# Main.net
KiCad netlist of a schematic drawn in EAGLE
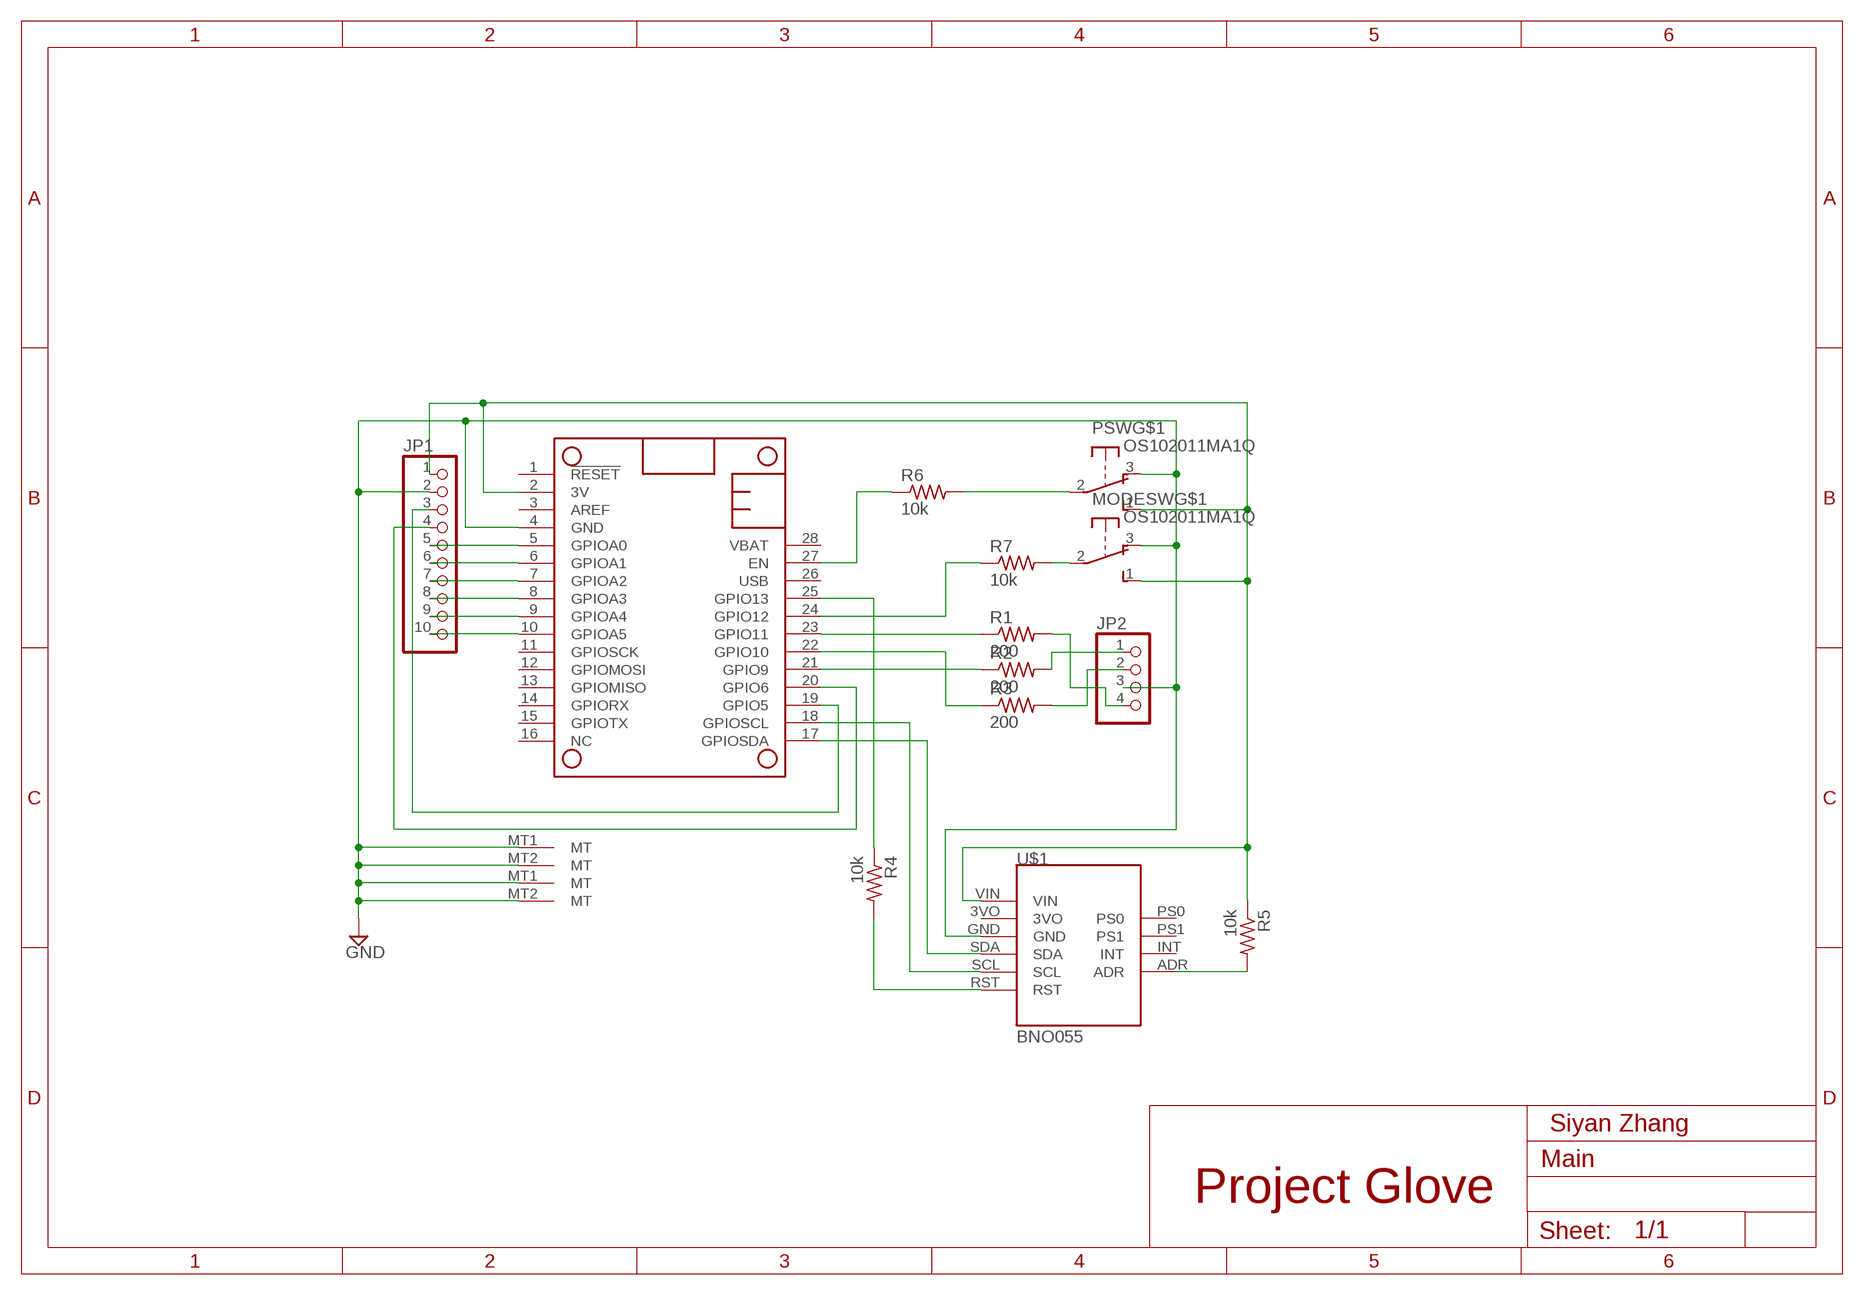
[diagram p0: schematic, sheet 1]

(export (version "E")
  (design (tool "Eeschema 10.0.6"))
  (components
    (comp (ref "JP1")
      (value "PINHD-1X10")
      (footprint "eagle-import:1X10")
      (libsource (lib "eagle-import") (part "PINHD-1X10"))
    )
    (comp (ref "JP2")
      (value "PINHD-1X4")
      (footprint "eagle-import:1X04")
      (libsource (lib "eagle-import") (part "PINHD-1X4"))
    )
    (comp (ref "MODESW")
      (value "OS102011MA1Q")
      (footprint "eagle-import:OS102011MA1Q")
      (libsource (lib "eagle-import") (part "OS102011MA1Q"))
    )
    (comp (ref "MS1")
      (value "FEATHERWING")
      (footprint "eagle-import:FEATHERWING")
      (libsource (lib "eagle-import") (part "FEATHERWING"))
    )
    (comp (ref "PSW")
      (value "OS102011MA1Q")
      (footprint "eagle-import:OS102011MA1Q")
      (libsource (lib "eagle-import") (part "OS102011MA1Q"))
    )
    (comp (ref "R1")
      (value "200")
      (footprint "eagle-import:0207_7")
      (libsource (lib "eagle-import") (part "R-US_0207/7"))
    )
    (comp (ref "R2")
      (value "200")
      (footprint "eagle-import:0207_7")
      (libsource (lib "eagle-import") (part "R-US_0207/7"))
    )
    (comp (ref "R3")
      (value "200")
      (footprint "eagle-import:0207_7")
      (libsource (lib "eagle-import") (part "R-US_0207/7"))
    )
    (comp (ref "R4")
      (value "10k")
      (footprint "eagle-import:0207_7")
      (libsource (lib "eagle-import") (part "R-US_0207/7"))
    )
    (comp (ref "R5")
      (value "10k")
      (footprint "eagle-import:0207_15")
      (libsource (lib "eagle-import") (part "R-US_0207/15"))
    )
    (comp (ref "R6")
      (value "10k")
      (footprint "eagle-import:0207_7")
      (libsource (lib "eagle-import") (part "R-US_0207/7"))
    )
    (comp (ref "R7")
      (value "10k")
      (footprint "eagle-import:0207_7")
      (libsource (lib "eagle-import") (part "R-US_0207/7"))
    )
    (comp (ref "U$1")
      (value "BNO055")
      (footprint "eagle-import:BNO055")
      (libsource (lib "eagle-import") (part "BNO055"))
    )
  )
  (nets
    (net (code "1") (name "/USB") (class "Default")
      (node (ref "MS1") (pin "26") (pinfunction "USB_26") (pintype "power_in"))
    )
    (net (code "2") (name "/VBAT") (class "Default")
      (node (ref "MS1") (pin "28") (pinfunction "VBAT_28") (pintype "power_in"))
    )
    (net (code "3") (name "GND") (class "Default")
      (node (ref "JP1") (pin "2") (pinfunction "2_2") (pintype "passive"))
      (node (ref "JP2") (pin "3") (pinfunction "3_3") (pintype "passive"))
      (node (ref "MODESW") (pin "3") (pinfunction "O_3") (pintype "passive"))
      (node (ref "MODESW") (pin "MT1") (pinfunction "MT_MT1") (pintype "passive"))
      (node (ref "MODESW") (pin "MT2") (pinfunction "MT_MT2") (pintype "passive"))
      (node (ref "MS1") (pin "4") (pinfunction "GND_4") (pintype "power_in"))
      (node (ref "PSW") (pin "3") (pinfunction "O_3") (pintype "passive"))
      (node (ref "PSW") (pin "MT1") (pinfunction "MT_MT1") (pintype "passive"))
      (node (ref "PSW") (pin "MT2") (pinfunction "MT_MT2") (pintype "passive"))
      (node (ref "U$1") (pin "GND") (pinfunction "GND_GND") (pintype "input"))
    )
    (net (code "4") (name "Net-(JP2-Pad1)") (class "Default")
      (node (ref "JP2") (pin "1") (pinfunction "1_1") (pintype "passive"))
      (node (ref "R2") (pin "2") (pinfunction "2_2") (pintype "passive"))
    )
    (net (code "5") (name "Net-(JP2-Pad2)") (class "Default")
      (node (ref "JP2") (pin "2") (pinfunction "2_2") (pintype "passive"))
      (node (ref "R3") (pin "2") (pinfunction "2_2") (pintype "passive"))
    )
    (net (code "6") (name "Net-(JP2-Pad4)") (class "Default")
      (node (ref "JP2") (pin "4") (pinfunction "4_4") (pintype "passive"))
      (node (ref "R1") (pin "2") (pinfunction "2_2") (pintype "passive"))
    )
    (net (code "7") (name "Net-(MODESWA-P)") (class "Default")
      (node (ref "MODESW") (pin "2") (pinfunction "P_2") (pintype "passive"))
      (node (ref "R7") (pin "2") (pinfunction "2_2") (pintype "passive"))
    )
    (net (code "8") (name "Net-(MODESWA-S)") (class "Default")
      (node (ref "JP1") (pin "1") (pinfunction "1_1") (pintype "passive"))
      (node (ref "MODESW") (pin "1") (pinfunction "S_1") (pintype "passive"))
      (node (ref "MS1") (pin "2") (pinfunction "3V_2") (pintype "power_in"))
      (node (ref "PSW") (pin "1") (pinfunction "S_1") (pintype "passive"))
      (node (ref "R5") (pin "1") (pinfunction "1_1") (pintype "passive"))
      (node (ref "U$1") (pin "VIN") (pinfunction "VIN_VIN") (pintype "input"))
    )
    (net (code "9") (name "Net-(MS1-EN)") (class "Default")
      (node (ref "MS1") (pin "27") (pinfunction "EN_27") (pintype "passive"))
      (node (ref "R6") (pin "1") (pinfunction "1_1") (pintype "passive"))
    )
    (net (code "10") (name "Net-(MS1-GPIO5)") (class "Default")
      (node (ref "JP1") (pin "3") (pinfunction "3_3") (pintype "passive"))
      (node (ref "MS1") (pin "19") (pinfunction "GPIO5_19") (pintype "bidirectional"))
    )
    (net (code "11") (name "Net-(MS1-GPIO6)") (class "Default")
      (node (ref "JP1") (pin "4") (pinfunction "4_4") (pintype "passive"))
      (node (ref "MS1") (pin "20") (pinfunction "GPIO6_20") (pintype "bidirectional"))
    )
    (net (code "12") (name "Net-(MS1-GPIO9)") (class "Default")
      (node (ref "MS1") (pin "21") (pinfunction "GPIO9_21") (pintype "bidirectional"))
      (node (ref "R2") (pin "1") (pinfunction "1_1") (pintype "passive"))
    )
    (net (code "13") (name "Net-(MS1-GPIO10)") (class "Default")
      (node (ref "MS1") (pin "22") (pinfunction "GPIO10_22") (pintype "bidirectional"))
      (node (ref "R3") (pin "1") (pinfunction "1_1") (pintype "passive"))
    )
    (net (code "14") (name "Net-(MS1-GPIO11)") (class "Default")
      (node (ref "MS1") (pin "23") (pinfunction "GPIO11_23") (pintype "bidirectional"))
      (node (ref "R1") (pin "1") (pinfunction "1_1") (pintype "passive"))
    )
    (net (code "15") (name "Net-(MS1-GPIO12)") (class "Default")
      (node (ref "MS1") (pin "24") (pinfunction "GPIO12_24") (pintype "bidirectional"))
      (node (ref "R7") (pin "1") (pinfunction "1_1") (pintype "passive"))
    )
    (net (code "16") (name "Net-(MS1-GPIO13)") (class "Default")
      (node (ref "MS1") (pin "25") (pinfunction "GPIO13_25") (pintype "bidirectional"))
      (node (ref "R4") (pin "1") (pinfunction "1_1") (pintype "passive"))
    )
    (net (code "17") (name "Net-(MS1-GPIOA0)") (class "Default")
      (node (ref "JP1") (pin "5") (pinfunction "5_5") (pintype "passive"))
      (node (ref "MS1") (pin "5") (pinfunction "GPIOA0_5") (pintype "bidirectional"))
    )
    (net (code "18") (name "Net-(MS1-GPIOA1)") (class "Default")
      (node (ref "JP1") (pin "6") (pinfunction "6_6") (pintype "passive"))
      (node (ref "MS1") (pin "6") (pinfunction "GPIOA1_6") (pintype "bidirectional"))
    )
    (net (code "19") (name "Net-(MS1-GPIOA2)") (class "Default")
      (node (ref "JP1") (pin "7") (pinfunction "7_7") (pintype "passive"))
      (node (ref "MS1") (pin "7") (pinfunction "GPIOA2_7") (pintype "bidirectional"))
    )
    (net (code "20") (name "Net-(MS1-GPIOA3)") (class "Default")
      (node (ref "JP1") (pin "8") (pinfunction "8_8") (pintype "passive"))
      (node (ref "MS1") (pin "8") (pinfunction "GPIOA3_8") (pintype "bidirectional"))
    )
    (net (code "21") (name "Net-(MS1-GPIOA4)") (class "Default")
      (node (ref "JP1") (pin "9") (pinfunction "9_9") (pintype "passive"))
      (node (ref "MS1") (pin "9") (pinfunction "GPIOA4_9") (pintype "bidirectional"))
    )
    (net (code "22") (name "Net-(MS1-GPIOA5)") (class "Default")
      (node (ref "JP1") (pin "10") (pinfunction "10_10") (pintype "passive"))
      (node (ref "MS1") (pin "10") (pinfunction "GPIOA5_10") (pintype "bidirectional"))
    )
    (net (code "23") (name "Net-(MS1-GPIOSCL)") (class "Default")
      (node (ref "MS1") (pin "18") (pinfunction "GPIOSCL_18") (pintype "bidirectional"))
      (node (ref "U$1") (pin "SCL") (pinfunction "SCL_SCL") (pintype "bidirectional"))
    )
    (net (code "24") (name "Net-(MS1-GPIOSDA)") (class "Default")
      (node (ref "MS1") (pin "17") (pinfunction "GPIOSDA_17") (pintype "bidirectional"))
      (node (ref "U$1") (pin "SDA") (pinfunction "SDA_SDA") (pintype "bidirectional"))
    )
    (net (code "25") (name "Net-(PSWA-P)") (class "Default")
      (node (ref "PSW") (pin "2") (pinfunction "P_2") (pintype "passive"))
      (node (ref "R6") (pin "2") (pinfunction "2_2") (pintype "passive"))
    )
    (net (code "26") (name "Net-(R4-Pad2)") (class "Default")
      (node (ref "R4") (pin "2") (pinfunction "2_2") (pintype "passive"))
      (node (ref "U$1") (pin "RST") (pinfunction "RST_RST") (pintype "input"))
    )
    (net (code "27") (name "Net-(R5-Pad2)") (class "Default")
      (node (ref "R5") (pin "2") (pinfunction "2_2") (pintype "passive"))
      (node (ref "U$1") (pin "ADR") (pinfunction "ADR_ADR") (pintype "input"))
    )
    (net (code "28") (name "unconnected-(MS1-AREF-Pad3)") (class "Default")
      (node (ref "MS1") (pin "3") (pinfunction "AREF_3") (pintype "passive"))
    )
    (net (code "29") (name "unconnected-(MS1-GPIOMISO-Pad13)") (class "Default")
      (node (ref "MS1") (pin "13") (pinfunction "GPIOMISO_13") (pintype "bidirectional"))
    )
    (net (code "30") (name "unconnected-(MS1-GPIOMOSI-Pad12)") (class "Default")
      (node (ref "MS1") (pin "12") (pinfunction "GPIOMOSI_12") (pintype "bidirectional"))
    )
    (net (code "31") (name "unconnected-(MS1-GPIORX-Pad14)") (class "Default")
      (node (ref "MS1") (pin "14") (pinfunction "GPIORX_14") (pintype "bidirectional"))
    )
    (net (code "32") (name "unconnected-(MS1-GPIOSCK-Pad11)") (class "Default")
      (node (ref "MS1") (pin "11") (pinfunction "GPIOSCK_11") (pintype "bidirectional"))
    )
    (net (code "33") (name "unconnected-(MS1-GPIOTX-Pad15)") (class "Default")
      (node (ref "MS1") (pin "15") (pinfunction "GPIOTX_15") (pintype "bidirectional"))
    )
    (net (code "34") (name "unconnected-(MS1-NC-Pad16)") (class "Default")
      (node (ref "MS1") (pin "16") (pinfunction "NC_16") (pintype "passive"))
    )
    (net (code "35") (name "unconnected-(MS1-~{RESET}-Pad1)") (class "Default")
      (node (ref "MS1") (pin "1") (pinfunction "~{RESET}_1") (pintype "input"))
    )
    (net (code "36") (name "unconnected-(U$1-Pad3VO)") (class "Default")
      (node (ref "U$1") (pin "3VO") (pinfunction "3VO_3VO") (pintype "output"))
    )
    (net (code "37") (name "unconnected-(U$1-PadINT)") (class "Default")
      (node (ref "U$1") (pin "INT") (pinfunction "INT_INT") (pintype "output"))
    )
    (net (code "38") (name "unconnected-(U$1-PadPS0)") (class "Default")
      (node (ref "U$1") (pin "PS0") (pinfunction "PS0_PS0") (pintype "input"))
    )
    (net (code "39") (name "unconnected-(U$1-PadPS1)") (class "Default")
      (node (ref "U$1") (pin "PS1") (pinfunction "PS1_PS1") (pintype "input"))
    )
  )
)
